# uController.net
KiCad netlist of a schematic drawn in Altium Designer
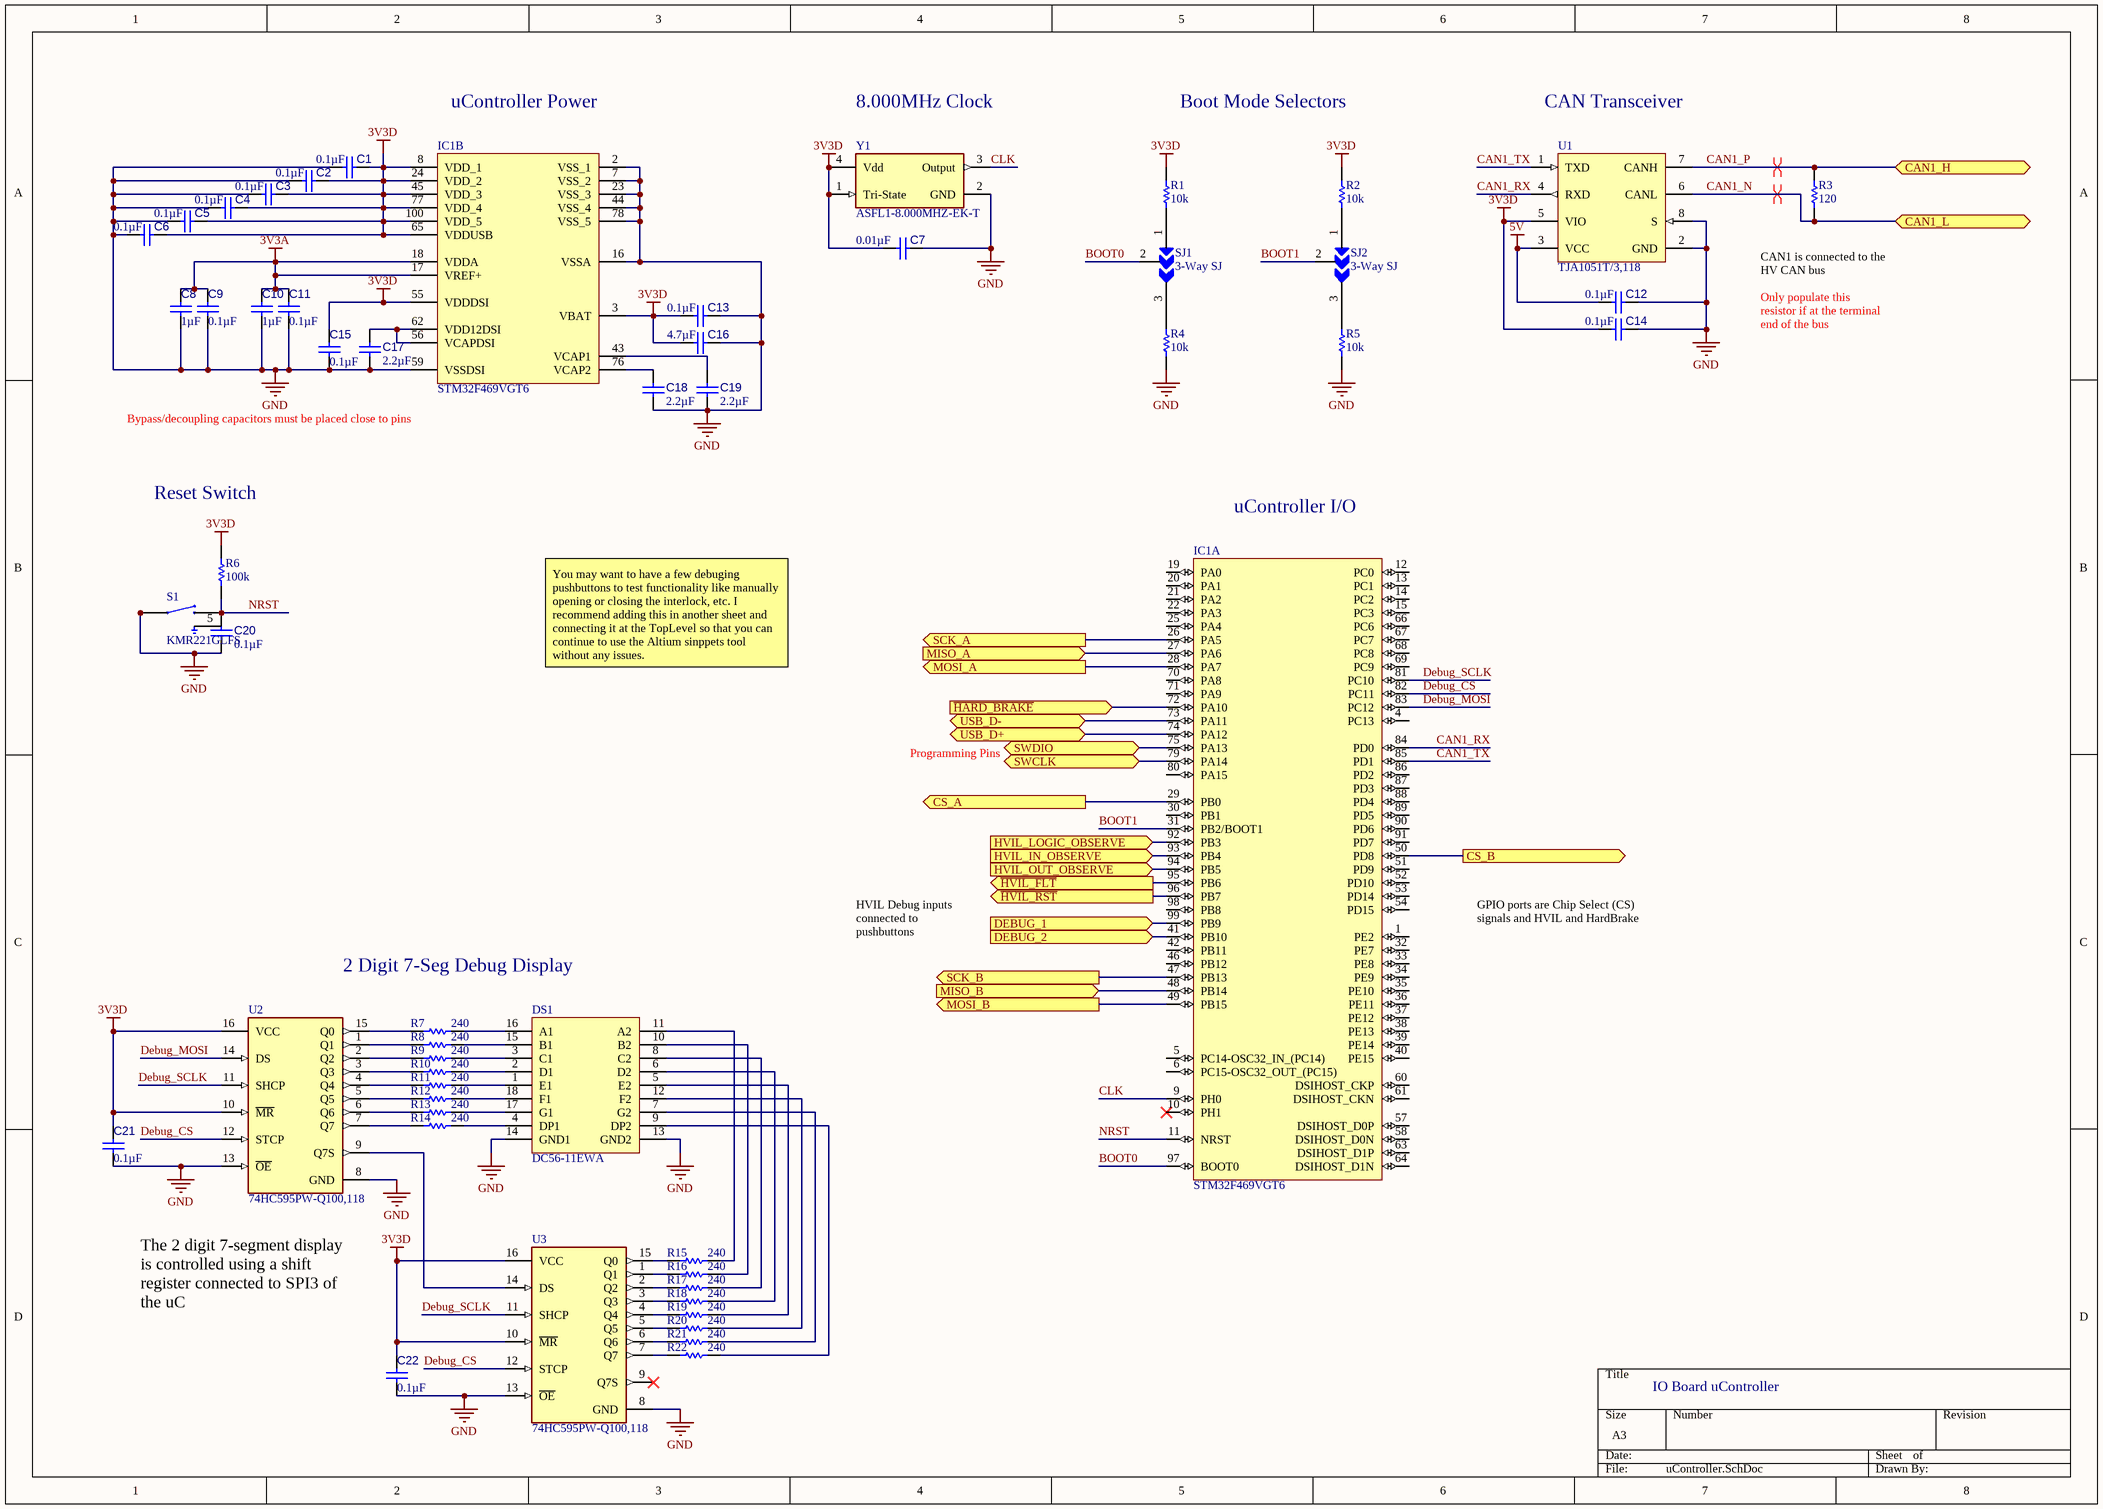
[diagram p0: uController.SchDoc]

(export (version "E")
  (design (tool "Eeschema 10.0.6"))
  (components
    (comp (ref "C1")
      (value "0.1µF")
      (footprint "CAPC2013X145X50ML20T25")
      (description "Chip Capacitor, 0.1 uF, +/-10%, 25 V, 0805 (2012 Metric)")
      (fields
        (field (name "MANUFACTURER") "KEMET")
        (field (name "MANUFACTURER PART NUMBER") "C0805C104K3RACTU")
      )
      (libsource (lib "Caltech FSAE") (part "CAP-NP-2"))
    )
    (comp (ref "C2")
      (value "0.1µF")
      (footprint "CAPC2013X145X50ML20T25")
      (description "Chip Capacitor, 0.1 uF, +/-10%, 25 V, 0805 (2012 Metric)")
      (fields
        (field (name "MANUFACTURER") "KEMET")
        (field (name "MANUFACTURER PART NUMBER") "C0805C104K3RACTU")
      )
      (libsource (lib "Caltech FSAE") (part "CAP-NP-2"))
    )
    (comp (ref "C3")
      (value "0.1µF")
      (footprint "CAPC2013X145X50ML20T25")
      (description "Chip Capacitor, 0.1 uF, +/-10%, 25 V, 0805 (2012 Metric)")
      (fields
        (field (name "MANUFACTURER") "KEMET")
        (field (name "MANUFACTURER PART NUMBER") "C0805C104K3RACTU")
      )
      (libsource (lib "Caltech FSAE") (part "CAP-NP-2"))
    )
    (comp (ref "C4")
      (value "0.1µF")
      (footprint "CAPC2013X145X50ML20T25")
      (description "Chip Capacitor, 0.1 uF, +/-10%, 25 V, 0805 (2012 Metric)")
      (fields
        (field (name "MANUFACTURER") "KEMET")
        (field (name "MANUFACTURER PART NUMBER") "C0805C104K3RACTU")
      )
      (libsource (lib "Caltech FSAE") (part "CAP-NP-2"))
    )
    (comp (ref "C5")
      (value "0.1µF")
      (footprint "CAPC2013X145X50ML20T25")
      (description "Chip Capacitor, 0.1 uF, +/-10%, 25 V, 0805 (2012 Metric)")
      (fields
        (field (name "MANUFACTURER") "KEMET")
        (field (name "MANUFACTURER PART NUMBER") "C0805C104K3RACTU")
      )
      (libsource (lib "Caltech FSAE") (part "CAP-NP-2"))
    )
    (comp (ref "C6")
      (value "0.1µF")
      (footprint "CAPC2013X145X50ML20T25")
      (description "Chip Capacitor, 0.1 uF, +/-10%, 25 V, 0805 (2012 Metric)")
      (fields
        (field (name "MANUFACTURER") "KEMET")
        (field (name "MANUFACTURER PART NUMBER") "C0805C104K3RACTU")
      )
      (libsource (lib "Caltech FSAE") (part "CAP-NP-2"))
    )
    (comp (ref "C7")
      (value "0.01µF")
      (footprint "CAPC2013X145X50ML20T25")
      (description "Chip Capacitor, 0.01 uF, +/-10%, 25 V, 0805 (2012 Metric)")
      (fields
        (field (name "MANUFACTURER") "KEMET")
        (field (name "MANUFACTURER PART NUMBER") "C0805C103K3RACTU")
      )
      (libsource (lib "Caltech FSAE") (part "CAP-NP-2"))
    )
    (comp (ref "C8")
      (value "1µF")
      (footprint "CAPC2013X145X50ML20T25")
      (description "Chip Capacitor, 1 uF, +/-10%, 25 V, 0805 (2012 Metric)")
      (fields
        (field (name "MANUFACTURER") "KEMET")
        (field (name "MANUFACTURER PART NUMBER") "C0805C105K3RACTU")
      )
      (libsource (lib "Caltech FSAE") (part "CAP-NP-2"))
    )
    (comp (ref "C9")
      (value "0.1µF")
      (footprint "CAPC2013X145X50ML20T25")
      (description "Chip Capacitor, 0.1 uF, +/-10%, 25 V, 0805 (2012 Metric)")
      (fields
        (field (name "MANUFACTURER") "KEMET")
        (field (name "MANUFACTURER PART NUMBER") "C0805C104K3RACTU")
      )
      (libsource (lib "Caltech FSAE") (part "CAP-NP-2"))
    )
    (comp (ref "C10")
      (value "1µF")
      (footprint "CAPC2013X145X50ML20T25")
      (description "Chip Capacitor, 1 uF, +/-10%, 25 V, 0805 (2012 Metric)")
      (fields
        (field (name "MANUFACTURER") "KEMET")
        (field (name "MANUFACTURER PART NUMBER") "C0805C105K3RACTU")
      )
      (libsource (lib "Caltech FSAE") (part "CAP-NP-2"))
    )
    (comp (ref "C11")
      (value "0.1µF")
      (footprint "CAPC2013X145X50ML20T25")
      (description "Chip Capacitor, 0.1 uF, +/-10%, 25 V, 0805 (2012 Metric)")
      (fields
        (field (name "MANUFACTURER") "KEMET")
        (field (name "MANUFACTURER PART NUMBER") "C0805C104K3RACTU")
      )
      (libsource (lib "Caltech FSAE") (part "CAP-NP-2"))
    )
    (comp (ref "C12")
      (value "0.1µF")
      (footprint "CAPC2013X145X50ML20T25")
      (description "Chip Capacitor, 0.1 uF, +/-10%, 25 V, 0805 (2012 Metric)")
      (fields
        (field (name "MANUFACTURER") "KEMET")
        (field (name "MANUFACTURER PART NUMBER") "C0805C104K3RACTU")
      )
      (libsource (lib "Caltech FSAE") (part "CAP-NP-2"))
    )
    (comp (ref "C13")
      (value "0.1µF")
      (footprint "CAPC2013X145X50ML20T25")
      (description "Chip Capacitor, 0.1 uF, +/-10%, 25 V, 0805 (2012 Metric)")
      (fields
        (field (name "MANUFACTURER") "KEMET")
        (field (name "MANUFACTURER PART NUMBER") "C0805C104K3RACTU")
      )
      (libsource (lib "Caltech FSAE") (part "CAP-NP-2"))
    )
    (comp (ref "C14")
      (value "0.1µF")
      (footprint "CAPC2013X145X50ML20T25")
      (description "Chip Capacitor, 0.1 uF, +/-10%, 25 V, 0805 (2012 Metric)")
      (fields
        (field (name "MANUFACTURER") "KEMET")
        (field (name "MANUFACTURER PART NUMBER") "C0805C104K3RACTU")
      )
      (libsource (lib "Caltech FSAE") (part "CAP-NP-2"))
    )
    (comp (ref "C15")
      (value "0.1µF")
      (footprint "CAPC2013X145X50ML20T25")
      (description "Chip Capacitor, 0.1 uF, +/-10%, 25 V, 0805 (2012 Metric)")
      (fields
        (field (name "MANUFACTURER") "KEMET")
        (field (name "MANUFACTURER PART NUMBER") "C0805C104K3RACTU")
      )
      (libsource (lib "Caltech FSAE") (part "CAP-NP-2"))
    )
    (comp (ref "C16")
      (value "4.7µF")
      (footprint "CAPC2013X145X50ML20T25")
      (description "Chip Capacitor, 4.7 uF, +/-10%, 25 V, 0805 (2012 Metric)")
      (fields
        (field (name "MANUFACTURER") "KEMET")
        (field (name "MANUFACTURER PART NUMBER") "C0805C475K3PACTU")
      )
      (libsource (lib "Caltech FSAE") (part "CAP-NP-2"))
    )
    (comp (ref "C17")
      (value "2.2µF")
      (footprint "CAPC2013X145X50ML20T25")
      (description "Chip Capacitor, 2.2 uF, +/-10%, 25 V, 0805 (2012 Metric)")
      (fields
        (field (name "MANUFACTURER") "KEMET")
        (field (name "MANUFACTURER PART NUMBER") "C0805C225K3RACTU")
      )
      (libsource (lib "Caltech FSAE") (part "CAP-NP-2"))
    )
    (comp (ref "C18")
      (value "2.2µF")
      (footprint "CAPC2013X145X50ML20T25")
      (description "Chip Capacitor, 2.2 uF, +/-10%, 25 V, 0805 (2012 Metric)")
      (fields
        (field (name "MANUFACTURER") "KEMET")
        (field (name "MANUFACTURER PART NUMBER") "C0805C225K3RACTU")
      )
      (libsource (lib "Caltech FSAE") (part "CAP-NP-2"))
    )
    (comp (ref "C19")
      (value "2.2µF")
      (footprint "CAPC2013X145X50ML20T25")
      (description "Chip Capacitor, 2.2 uF, +/-10%, 25 V, 0805 (2012 Metric)")
      (fields
        (field (name "MANUFACTURER") "KEMET")
        (field (name "MANUFACTURER PART NUMBER") "C0805C225K3RACTU")
      )
      (libsource (lib "Caltech FSAE") (part "CAP-NP-2"))
    )
    (comp (ref "C20")
      (value "0.1µF")
      (footprint "CAPC2013X145X50ML20T25")
      (description "Chip Capacitor, 0.1 uF, +/-10%, 25 V, 0805 (2012 Metric)")
      (fields
        (field (name "MANUFACTURER") "KEMET")
        (field (name "MANUFACTURER PART NUMBER") "C0805C104K3RACTU")
      )
      (libsource (lib "Caltech FSAE") (part "CAP-NP-2"))
    )
    (comp (ref "C21")
      (value "0.1µF")
      (footprint "CAPC2013X145X50ML20T25")
      (description "Chip Capacitor, 0.1 uF, +/-10%, 25 V, 0805 (2012 Metric)")
      (fields
        (field (name "MANUFACTURER") "KEMET")
        (field (name "MANUFACTURER PART NUMBER") "C0805C104K3RACTU")
      )
      (libsource (lib "Caltech FSAE") (part "CAP-NP-2"))
    )
    (comp (ref "C22")
      (value "0.1µF")
      (footprint "CAPC2013X145X50ML20T25")
      (description "Chip Capacitor, 0.1 uF, +/-10%, 25 V, 0805 (2012 Metric)")
      (fields
        (field (name "MANUFACTURER") "KEMET")
        (field (name "MANUFACTURER PART NUMBER") "C0805C104K3RACTU")
      )
      (libsource (lib "Caltech FSAE") (part "CAP-NP-2"))
    )
    (comp (ref "DS1")
      (value "DC56-11EWA")
      (footprint "uControllerTemplate2021:DIPS1524W75P254L2500H825Q18N")
      (description "Display")
      (fields (field (name "MOUSER PART NUMBER") "604-DC56-11EWA"))
      (libsource (lib "uControllerTemplate2021") (part "DC56-11EWA"))
    )
    (comp (ref "IC1")
      (value "STM32F469VGT6")
      (footprint "uControllerTemplate2021:QFP50P1600X1600X160-100N")
      (description "Integrated Circuit")
      (fields (field (name "MOUSER PART NUMBER") "511-STM32F469VGT6"))
      (libsource (lib "uControllerTemplate2021") (part "STM32F469VGT6"))
    )
    (comp (ref "R1")
      (value "10k")
      (footprint "RESC2013X50X35ML15T15")
      (description "Chip Resistor, 10k Ohm, +/- 1%, 125 mW, -55 to 155 degC, 0805 (2012 Metric)")
      (fields
        (field (name "MANUFACTURER") "Yageo")
        (field (name "MANUFACTURER PART NUMBER") "RC0805FR-0710KL")
      )
      (libsource (lib "Caltech FSAE") (part "RES-2"))
    )
    (comp (ref "R2")
      (value "10k")
      (footprint "RESC2013X50X35ML15T15")
      (description "Chip Resistor, 10k Ohm, +/- 1%, 125 mW, -55 to 155 degC, 0805 (2012 Metric)")
      (fields
        (field (name "MANUFACTURER") "Yageo")
        (field (name "MANUFACTURER PART NUMBER") "RC0805FR-0710KL")
      )
      (libsource (lib "Caltech FSAE") (part "RES-2"))
    )
    (comp (ref "R3")
      (value "120")
      (footprint "RESC2013X50X35ML15T15")
      (description "Chip Resistor, 120 Ohm, +/- 1%, 125 mW, -55 to 155 degC, 0805 (2012 Metric)")
      (fields
        (field (name "MANUFACTURER") "TE Connectivity")
        (field (name "MANUFACTURER PART NUMBER") "CRGCQ0805F120R")
      )
      (libsource (lib "Caltech FSAE") (part "RES-2"))
    )
    (comp (ref "R4")
      (value "10k")
      (footprint "RESC2013X50X35ML15T15")
      (description "Chip Resistor, 10k Ohm, +/- 1%, 125 mW, -55 to 155 degC, 0805 (2012 Metric)")
      (fields
        (field (name "MANUFACTURER") "Yageo")
        (field (name "MANUFACTURER PART NUMBER") "RC0805FR-0710KL")
      )
      (libsource (lib "Caltech FSAE") (part "RES-2"))
    )
    (comp (ref "R5")
      (value "10k")
      (footprint "RESC2013X50X35ML15T15")
      (description "Chip Resistor, 10k Ohm, +/- 1%, 125 mW, -55 to 155 degC, 0805 (2012 Metric)")
      (fields
        (field (name "MANUFACTURER") "Yageo")
        (field (name "MANUFACTURER PART NUMBER") "RC0805FR-0710KL")
      )
      (libsource (lib "Caltech FSAE") (part "RES-2"))
    )
    (comp (ref "R6")
      (value "100k")
      (footprint "RESC2013X50X35ML15T15")
      (description "Chip Resistor, 100k Ohm, +/- 1%, 125 mW, -55 to 155 degC, 0805 (2012 Metric)")
      (fields
        (field (name "MANUFACTURER") "Yageo")
        (field (name "MANUFACTURER PART NUMBER") "RC0805FR-07100KL")
      )
      (libsource (lib "Caltech FSAE") (part "RES-2"))
    )
    (comp (ref "R7")
      (value "240")
      (footprint "RESC2013X50X35ML15T15")
      (description "Chip Resistor, 240 Ohm, +/- 1%, 125 mW, -55 to 155 degC, 0805 (2012 Metric)")
      (fields
        (field (name "MANUFACTURER") "Panasonic")
        (field (name "MANUFACTURER PART NUMBER") "ERA-6AEB241V")
      )
      (libsource (lib "Caltech FSAE") (part "RES-2"))
    )
    (comp (ref "R8")
      (value "240")
      (footprint "RESC2013X50X35ML15T15")
      (description "Chip Resistor, 240 Ohm, +/- 1%, 125 mW, -55 to 155 degC, 0805 (2012 Metric)")
      (fields
        (field (name "MANUFACTURER") "Panasonic")
        (field (name "MANUFACTURER PART NUMBER") "ERA-6AEB241V")
      )
      (libsource (lib "Caltech FSAE") (part "RES-2"))
    )
    (comp (ref "R9")
      (value "240")
      (footprint "RESC2013X50X35ML15T15")
      (description "Chip Resistor, 240 Ohm, +/- 1%, 125 mW, -55 to 155 degC, 0805 (2012 Metric)")
      (fields
        (field (name "MANUFACTURER") "Panasonic")
        (field (name "MANUFACTURER PART NUMBER") "ERA-6AEB241V")
      )
      (libsource (lib "Caltech FSAE") (part "RES-2"))
    )
    (comp (ref "R10")
      (value "240")
      (footprint "RESC2013X50X35ML15T15")
      (description "Chip Resistor, 240 Ohm, +/- 1%, 125 mW, -55 to 155 degC, 0805 (2012 Metric)")
      (fields
        (field (name "MANUFACTURER") "Panasonic")
        (field (name "MANUFACTURER PART NUMBER") "ERA-6AEB241V")
      )
      (libsource (lib "Caltech FSAE") (part "RES-2"))
    )
    (comp (ref "R11")
      (value "240")
      (footprint "RESC2013X50X35ML15T15")
      (description "Chip Resistor, 240 Ohm, +/- 1%, 125 mW, -55 to 155 degC, 0805 (2012 Metric)")
      (fields
        (field (name "MANUFACTURER") "Panasonic")
        (field (name "MANUFACTURER PART NUMBER") "ERA-6AEB241V")
      )
      (libsource (lib "Caltech FSAE") (part "RES-2"))
    )
    (comp (ref "R12")
      (value "240")
      (footprint "RESC2013X50X35ML15T15")
      (description "Chip Resistor, 240 Ohm, +/- 1%, 125 mW, -55 to 155 degC, 0805 (2012 Metric)")
      (fields
        (field (name "MANUFACTURER") "Panasonic")
        (field (name "MANUFACTURER PART NUMBER") "ERA-6AEB241V")
      )
      (libsource (lib "Caltech FSAE") (part "RES-2"))
    )
    (comp (ref "R13")
      (value "240")
      (footprint "RESC2013X50X35ML15T15")
      (description "Chip Resistor, 240 Ohm, +/- 1%, 125 mW, -55 to 155 degC, 0805 (2012 Metric)")
      (fields
        (field (name "MANUFACTURER") "Panasonic")
        (field (name "MANUFACTURER PART NUMBER") "ERA-6AEB241V")
      )
      (libsource (lib "Caltech FSAE") (part "RES-2"))
    )
    (comp (ref "R14")
      (value "240")
      (footprint "RESC2013X50X35ML15T15")
      (description "Chip Resistor, 240 Ohm, +/- 1%, 125 mW, -55 to 155 degC, 0805 (2012 Metric)")
      (fields
        (field (name "MANUFACTURER") "Panasonic")
        (field (name "MANUFACTURER PART NUMBER") "ERA-6AEB241V")
      )
      (libsource (lib "Caltech FSAE") (part "RES-2"))
    )
    (comp (ref "R15")
      (value "240")
      (footprint "RESC2013X50X35ML15T15")
      (description "Chip Resistor, 240 Ohm, +/- 1%, 125 mW, -55 to 155 degC, 0805 (2012 Metric)")
      (fields
        (field (name "MANUFACTURER") "Panasonic")
        (field (name "MANUFACTURER PART NUMBER") "ERA-6AEB241V")
      )
      (libsource (lib "Caltech FSAE") (part "RES-2"))
    )
    (comp (ref "R16")
      (value "240")
      (footprint "RESC2013X50X35ML15T15")
      (description "Chip Resistor, 240 Ohm, +/- 1%, 125 mW, -55 to 155 degC, 0805 (2012 Metric)")
      (fields
        (field (name "MANUFACTURER") "Panasonic")
        (field (name "MANUFACTURER PART NUMBER") "ERA-6AEB241V")
      )
      (libsource (lib "Caltech FSAE") (part "RES-2"))
    )
    (comp (ref "R17")
      (value "240")
      (footprint "RESC2013X50X35ML15T15")
      (description "Chip Resistor, 240 Ohm, +/- 1%, 125 mW, -55 to 155 degC, 0805 (2012 Metric)")
      (fields
        (field (name "MANUFACTURER") "Panasonic")
        (field (name "MANUFACTURER PART NUMBER") "ERA-6AEB241V")
      )
      (libsource (lib "Caltech FSAE") (part "RES-2"))
    )
    (comp (ref "R18")
      (value "240")
      (footprint "RESC2013X50X35ML15T15")
      (description "Chip Resistor, 240 Ohm, +/- 1%, 125 mW, -55 to 155 degC, 0805 (2012 Metric)")
      (fields
        (field (name "MANUFACTURER") "Panasonic")
        (field (name "MANUFACTURER PART NUMBER") "ERA-6AEB241V")
      )
      (libsource (lib "Caltech FSAE") (part "RES-2"))
    )
    (comp (ref "R19")
      (value "240")
      (footprint "RESC2013X50X35ML15T15")
      (description "Chip Resistor, 240 Ohm, +/- 1%, 125 mW, -55 to 155 degC, 0805 (2012 Metric)")
      (fields
        (field (name "MANUFACTURER") "Panasonic")
        (field (name "MANUFACTURER PART NUMBER") "ERA-6AEB241V")
      )
      (libsource (lib "Caltech FSAE") (part "RES-2"))
    )
    (comp (ref "R20")
      (value "240")
      (footprint "RESC2013X50X35ML15T15")
      (description "Chip Resistor, 240 Ohm, +/- 1%, 125 mW, -55 to 155 degC, 0805 (2012 Metric)")
      (fields
        (field (name "MANUFACTURER") "Panasonic")
        (field (name "MANUFACTURER PART NUMBER") "ERA-6AEB241V")
      )
      (libsource (lib "Caltech FSAE") (part "RES-2"))
    )
    (comp (ref "R21")
      (value "240")
      (footprint "RESC2013X50X35ML15T15")
      (description "Chip Resistor, 240 Ohm, +/- 1%, 125 mW, -55 to 155 degC, 0805 (2012 Metric)")
      (fields
        (field (name "MANUFACTURER") "Panasonic")
        (field (name "MANUFACTURER PART NUMBER") "ERA-6AEB241V")
      )
      (libsource (lib "Caltech FSAE") (part "RES-2"))
    )
    (comp (ref "R22")
      (value "240")
      (footprint "RESC2013X50X35ML15T15")
      (description "Chip Resistor, 240 Ohm, +/- 1%, 125 mW, -55 to 155 degC, 0805 (2012 Metric)")
      (fields
        (field (name "MANUFACTURER") "Panasonic")
        (field (name "MANUFACTURER PART NUMBER") "ERA-6AEB241V")
      )
      (libsource (lib "Caltech FSAE") (part "RES-2"))
    )
    (comp (ref "S1")
      (value "KMR221GLFS")
      (footprint "SW_KMR221GLFS")
      (description "Tactile Switch SPST-NO Top Actuated Surface Mount")
      (fields (field (name "MF") "C&K"))
      (libsource (lib "uControllerTemplate2021") (part "KMR221GLFS"))
    )
    (comp (ref "SJ1")
      (value "3-Way SJ")
      (footprint "3-Way SJ")
      (description "3-Way Solder Jumper")
      (libsource (lib "uControllerTemplate2021") (part "3-Way SJ"))
    )
    (comp (ref "SJ2")
      (value "3-Way SJ")
      (footprint "3-Way SJ")
      (description "3-Way Solder Jumper")
      (libsource (lib "uControllerTemplate2021") (part "3-Way SJ"))
    )
    (comp (ref "U1")
      (value "TJA1051T/3,118")
      (footprint "NXP-SOIC-8_L")
      (description "High-Speed CAN Transceiver, 3 to 5 V, 8-Pin SOIC (SOT96-1), RoHS, Tape and Reel")
      (fields (field (name "MANUFACTURER") "NXP"))
      (libsource (lib "Altium Content Vault") (part "NXP-TJA1051T_3-SOIC-8"))
    )
    (comp (ref "U2")
      (value "74HC595PW-Q100,118")
      (footprint "FP-SOT403-1-MFG")
      (description "IC SHIFT REGISTER 8BIT 16TSSOP")
      (fields
        (field (name "MANUFACTURER") "Nexperia")
        (field (name "OCTOPART") "https://octopart.com/74hc595pw-q100%2C118-nexperia-78737379")
      )
      (libsource (lib "Altium Content Vault") (part "35014dcb5ee7218ec7bb80311b7c79e"))
    )
    (comp (ref "U3")
      (value "74HC595PW-Q100,118")
      (footprint "FP-SOT403-1-MFG")
      (description "IC SHIFT REGISTER 8BIT 16TSSOP")
      (fields
        (field (name "MANUFACTURER") "Nexperia")
        (field (name "OCTOPART") "https://octopart.com/74hc595pw-q100%2C118-nexperia-78737379")
      )
      (libsource (lib "Altium Content Vault") (part "35014dcb5ee7218ec7bb80311b7c79e"))
    )
    (comp (ref "Y1")
      (value "ASFL1-8.000MHZ-EK-T")
      (footprint "FP-ASFL1-MFG")
      (description "XTAL OSC XO 8.000MHZ HCMOS TTL")
      (fields
        (field (name "OCTOPART") "https://octopart.com/asfl1-16.384mhz-ec-t-abracon-317624")
        (field (name "MANUFACTURER") "Abracon")
      )
      (libsource (lib "Altium Content Vault") (part "4040d53610bfd20b859c6f7b79dc732"))
    )
  )
  (nets
    (net (code "1") (name "/BOOT0") (class "Default")
      (node (ref "IC1") (pin "97") (pinfunction "BOOT0_97") (pintype "bidirectional"))
      (node (ref "SJ1") (pin "2") (pinfunction "2_2") (pintype "passive"))
    )
    (net (code "2") (name "/BOOT1") (class "Default")
      (node (ref "IC1") (pin "31") (pinfunction "PB2/BOOT1_31") (pintype "bidirectional"))
      (node (ref "SJ2") (pin "2") (pinfunction "2_2") (pintype "passive"))
    )
    (net (code "3") (name "/CAN1_N") (class "Default")
      (node (ref "R3") (pin "1") (pinfunction "1_1") (pintype "passive"))
      (node (ref "U1") (pin "6") (pinfunction "CANL_6") (pintype "passive"))
    )
    (net (code "4") (name "/CAN1_P") (class "Default")
      (node (ref "R3") (pin "2") (pinfunction "2_2") (pintype "passive"))
      (node (ref "U1") (pin "7") (pinfunction "CANH_7") (pintype "passive"))
    )
    (net (code "5") (name "/CAN1_RX") (class "Default")
      (node (ref "IC1") (pin "84") (pinfunction "PD0_84") (pintype "bidirectional"))
      (node (ref "U1") (pin "4") (pinfunction "RXD_4") (pintype "output"))
    )
    (net (code "6") (name "/CAN1_TX") (class "Default")
      (node (ref "IC1") (pin "85") (pinfunction "PD1_85") (pintype "bidirectional"))
      (node (ref "U1") (pin "1") (pinfunction "TXD_1") (pintype "input"))
    )
    (net (code "7") (name "/CLK") (class "Default")
      (node (ref "IC1") (pin "9") (pinfunction "PH0_9") (pintype "bidirectional"))
      (node (ref "Y1") (pin "3") (pinfunction "Output_3") (pintype "output"))
    )
    (net (code "8") (name "/CS_A") (class "Default")
      (node (ref "IC1") (pin "29") (pinfunction "PB0_29") (pintype "bidirectional"))
    )
    (net (code "9") (name "/CS_B") (class "Default")
      (node (ref "IC1") (pin "50") (pinfunction "PD8_50") (pintype "bidirectional"))
    )
    (net (code "10") (name "/DEBUG_1") (class "Default")
      (node (ref "IC1") (pin "99") (pinfunction "PB9_99") (pintype "bidirectional"))
    )
    (net (code "11") (name "/DEBUG_2") (class "Default")
      (node (ref "IC1") (pin "41") (pinfunction "PB10_41") (pintype "bidirectional"))
    )
    (net (code "12") (name "/Debug_CS") (class "Default")
      (node (ref "IC1") (pin "82") (pinfunction "PC11_82") (pintype "bidirectional"))
      (node (ref "U2") (pin "12") (pinfunction "STCP_12") (pintype "input"))
      (node (ref "U3") (pin "12") (pinfunction "STCP_12") (pintype "input"))
    )
    (net (code "13") (name "/Debug_MOSI") (class "Default")
      (node (ref "IC1") (pin "83") (pinfunction "PC12_83") (pintype "bidirectional"))
      (node (ref "U2") (pin "14") (pinfunction "DS_14") (pintype "input"))
    )
    (net (code "14") (name "/Debug_SCLK") (class "Default")
      (node (ref "IC1") (pin "81") (pinfunction "PC10_81") (pintype "bidirectional"))
      (node (ref "U2") (pin "11") (pinfunction "SHCP_11") (pintype "input"))
      (node (ref "U3") (pin "11") (pinfunction "SHCP_11") (pintype "input"))
    )
    (net (code "15") (name "/HVIL_IN_OBSERVE") (class "Default")
      (node (ref "IC1") (pin "93") (pinfunction "PB4_93") (pintype "bidirectional"))
    )
    (net (code "16") (name "/HVIL_LOGIC_OBSERVE") (class "Default")
      (node (ref "IC1") (pin "92") (pinfunction "PB3_92") (pintype "bidirectional"))
    )
    (net (code "17") (name "/HVIL_OUT_OBSERVE") (class "Default")
      (node (ref "IC1") (pin "94") (pinfunction "PB5_94") (pintype "bidirectional"))
    )
    (net (code "18") (name "/MISO_A") (class "Default")
      (node (ref "IC1") (pin "27") (pinfunction "PA6_27") (pintype "bidirectional"))
    )
    (net (code "19") (name "/MISO_B") (class "Default")
      (node (ref "IC1") (pin "48") (pinfunction "PB14_48") (pintype "bidirectional"))
    )
    (net (code "20") (name "/MOSI_A") (class "Default")
      (node (ref "IC1") (pin "28") (pinfunction "PA7_28") (pintype "bidirectional"))
    )
    (net (code "21") (name "/MOSI_B") (class "Default")
      (node (ref "IC1") (pin "49") (pinfunction "PB15_49") (pintype "bidirectional"))
    )
    (net (code "22") (name "/NRST") (class "Default")
      (node (ref "C20") (pin "2") (pinfunction "2_2") (pintype "passive"))
      (node (ref "IC1") (pin "11") (pinfunction "NRST_11") (pintype "bidirectional"))
      (node (ref "R6") (pin "1") (pinfunction "1_1") (pintype "passive"))
      (node (ref "S1") (pin "2") (pinfunction "3_2") (pintype "passive"))
      (node (ref "S1") (pin "3") (pinfunction "3_3") (pintype "passive"))
    )
    (net (code "23") (name "/SCK_A") (class "Default")
      (node (ref "IC1") (pin "26") (pinfunction "PA5_26") (pintype "bidirectional"))
    )
    (net (code "24") (name "/SCK_B") (class "Default")
      (node (ref "IC1") (pin "47") (pinfunction "PB13_47") (pintype "bidirectional"))
    )
    (net (code "25") (name "/SWCLK") (class "Default")
      (node (ref "IC1") (pin "79") (pinfunction "PA14_79") (pintype "bidirectional"))
    )
    (net (code "26") (name "/SWDIO") (class "Default")
      (node (ref "IC1") (pin "75") (pinfunction "PA13_75") (pintype "bidirectional"))
    )
    (net (code "27") (name "/USB_D+") (class "Default")
      (node (ref "IC1") (pin "74") (pinfunction "PA12_74") (pintype "bidirectional"))
    )
    (net (code "28") (name "/USB_D-") (class "Default")
      (node (ref "IC1") (pin "73") (pinfunction "PA11_73") (pintype "bidirectional"))
    )
    (net (code "29") (name "/~{HARD_BRAKE}") (class "Default")
      (node (ref "IC1") (pin "72") (pinfunction "PA10_72") (pintype "bidirectional"))
    )
    (net (code "30") (name "/~{HVIL_FLT}") (class "Default")
      (node (ref "IC1") (pin "95") (pinfunction "PB6_95") (pintype "bidirectional"))
    )
    (net (code "31") (name "/~{HVIL_RST}") (class "Default")
      (node (ref "IC1") (pin "96") (pinfunction "PB7_96") (pintype "bidirectional"))
    )
    (net (code "32") (name "3V3A") (class "Default")
      (node (ref "C10") (pin "2") (pinfunction "2_2") (pintype "passive"))
      (node (ref "C11") (pin "1") (pinfunction "1_1") (pintype "passive"))
      (node (ref "C8") (pin "2") (pinfunction "2_2") (pintype "passive"))
      (node (ref "C9") (pin "1") (pinfunction "1_1") (pintype "passive"))
      (node (ref "IC1") (pin "17") (pinfunction "VREF+_17") (pintype "passive"))
      (node (ref "IC1") (pin "18") (pinfunction "VDDA_18") (pintype "passive"))
    )
    (net (code "33") (name "3V3D") (class "Default")
      (node (ref "C1") (pin "2") (pinfunction "2_2") (pintype "passive"))
      (node (ref "C13") (pin "1") (pinfunction "1_1") (pintype "passive"))
      (node (ref "C14") (pin "1") (pinfunction "1_1") (pintype "passive"))
      (node (ref "C15") (pin "1") (pinfunction "1_1") (pintype "passive"))
      (node (ref "C16") (pin "1") (pinfunction "1_1") (pintype "passive"))
      (node (ref "C2") (pin "2") (pinfunction "2_2") (pintype "passive"))
      (node (ref "C21") (pin "1") (pinfunction "1_1") (pintype "passive"))
      (node (ref "C22") (pin "1") (pinfunction "1_1") (pintype "passive"))
      (node (ref "C3") (pin "2") (pinfunction "2_2") (pintype "passive"))
      (node (ref "C4") (pin "2") (pinfunction "2_2") (pintype "passive"))
      (node (ref "C5") (pin "2") (pinfunction "2_2") (pintype "passive"))
      (node (ref "C6") (pin "2") (pinfunction "2_2") (pintype "passive"))
      (node (ref "C7") (pin "1") (pinfunction "1_1") (pintype "passive"))
      (node (ref "IC1") (pin "100") (pinfunction "VDD_5_100") (pintype "passive"))
      (node (ref "IC1") (pin "24") (pinfunction "VDD_2_24") (pintype "passive"))
      (node (ref "IC1") (pin "3") (pinfunction "VBAT_3") (pintype "passive"))
      (node (ref "IC1") (pin "45") (pinfunction "VDD_3_45") (pintype "passive"))
      (node (ref "IC1") (pin "55") (pinfunction "VDDDSI_55") (pintype "passive"))
      (node (ref "IC1") (pin "65") (pinfunction "VDDUSB_65") (pintype "passive"))
      (node (ref "IC1") (pin "77") (pinfunction "VDD_4_77") (pintype "passive"))
      (node (ref "IC1") (pin "8") (pinfunction "VDD_1_8") (pintype "passive"))
      (node (ref "R1") (pin "2") (pinfunction "2_2") (pintype "passive"))
      (node (ref "R2") (pin "2") (pinfunction "2_2") (pintype "passive"))
      (node (ref "R6") (pin "2") (pinfunction "2_2") (pintype "passive"))
      (node (ref "U1") (pin "5") (pinfunction "VIO_5") (pintype "power_in"))
      (node (ref "U2") (pin "10") (pinfunction "~{MR}_10") (pintype "input"))
      (node (ref "U2") (pin "16") (pinfunction "VCC_16") (pintype "power_in"))
      (node (ref "U3") (pin "10") (pinfunction "~{MR}_10") (pintype "input"))
      (node (ref "U3") (pin "16") (pinfunction "VCC_16") (pintype "power_in"))
      (node (ref "Y1") (pin "1") (pinfunction "Tri-State_1") (pintype "input"))
      (node (ref "Y1") (pin "4") (pinfunction "Vdd_4") (pintype "power_in"))
    )
    (net (code "34") (name "5V") (class "Default")
      (node (ref "C12") (pin "1") (pinfunction "1_1") (pintype "passive"))
      (node (ref "U1") (pin "3") (pinfunction "VCC_3") (pintype "power_in"))
    )
    (net (code "35") (name "GND") (class "Default")
      (node (ref "C1") (pin "1") (pinfunction "1_1") (pintype "passive"))
      (node (ref "C10") (pin "1") (pinfunction "1_1") (pintype "passive"))
      (node (ref "C11") (pin "2") (pinfunction "2_2") (pintype "passive"))
      (node (ref "C12") (pin "2") (pinfunction "2_2") (pintype "passive"))
      (node (ref "C13") (pin "2") (pinfunction "2_2") (pintype "passive"))
      (node (ref "C14") (pin "2") (pinfunction "2_2") (pintype "passive"))
      (node (ref "C15") (pin "2") (pinfunction "2_2") (pintype "passive"))
      (node (ref "C16") (pin "2") (pinfunction "2_2") (pintype "passive"))
      (node (ref "C17") (pin "1") (pinfunction "1_1") (pintype "passive"))
      (node (ref "C18") (pin "1") (pinfunction "1_1") (pintype "passive"))
      (node (ref "C19") (pin "1") (pinfunction "1_1") (pintype "passive"))
      (node (ref "C2") (pin "1") (pinfunction "1_1") (pintype "passive"))
      (node (ref "C20") (pin "1") (pinfunction "1_1") (pintype "passive"))
      (node (ref "C21") (pin "2") (pinfunction "2_2") (pintype "passive"))
      (node (ref "C22") (pin "2") (pinfunction "2_2") (pintype "passive"))
      (node (ref "C3") (pin "1") (pinfunction "1_1") (pintype "passive"))
      (node (ref "C4") (pin "1") (pinfunction "1_1") (pintype "passive"))
      (node (ref "C5") (pin "1") (pinfunction "1_1") (pintype "passive"))
      (node (ref "C6") (pin "1") (pinfunction "1_1") (pintype "passive"))
      (node (ref "C7") (pin "2") (pinfunction "2_2") (pintype "passive"))
      (node (ref "C8") (pin "1") (pinfunction "1_1") (pintype "passive"))
      (node (ref "C9") (pin "2") (pinfunction "2_2") (pintype "passive"))
      (node (ref "DS1") (pin "13") (pinfunction "GND2_13") (pintype "passive"))
      (node (ref "DS1") (pin "14") (pinfunction "GND1_14") (pintype "passive"))
      (node (ref "IC1") (pin "16") (pinfunction "VSSA_16") (pintype "passive"))
      (node (ref "IC1") (pin "2") (pinfunction "VSS_1_2") (pintype "passive"))
      (node (ref "IC1") (pin "23") (pinfunction "VSS_3_23") (pintype "passive"))
      (node (ref "IC1") (pin "44") (pinfunction "VSS_4_44") (pintype "passive"))
      (node (ref "IC1") (pin "59") (pinfunction "VSSDSI_59") (pintype "passive"))
      (node (ref "IC1") (pin "7") (pinfunction "VSS_2_7") (pintype "passive"))
      (node (ref "IC1") (pin "78") (pinfunction "VSS_5_78") (pintype "passive"))
      (node (ref "R4") (pin "1") (pinfunction "1_1") (pintype "passive"))
      (node (ref "R5") (pin "1") (pinfunction "1_1") (pintype "passive"))
      (node (ref "S1") (pin "1") (pinfunction "1_1") (pintype "passive"))
      (node (ref "S1") (pin "4") (pinfunction "1_4") (pintype "passive"))
      (node (ref "U1") (pin "2") (pinfunction "GND_2") (pintype "power_in"))
      (node (ref "U1") (pin "8") (pinfunction "S_8") (pintype "input"))
      (node (ref "U2") (pin "13") (pinfunction "~{OE}_13") (pintype "input"))
      (node (ref "U2") (pin "8") (pinfunction "GND_8") (pintype "power_in"))
      (node (ref "U3") (pin "13") (pinfunction "~{OE}_13") (pintype "input"))
      (node (ref "U3") (pin "8") (pinfunction "GND_8") (pintype "power_in"))
      (node (ref "Y1") (pin "2") (pinfunction "GND_2") (pintype "power_in"))
    )
    (net (code "36") (name "Net-(DS1-A1)") (class "Default")
      (node (ref "DS1") (pin "16") (pinfunction "A1_16") (pintype "passive"))
      (node (ref "R7") (pin "1") (pinfunction "1_1") (pintype "passive"))
    )
    (net (code "37") (name "Net-(DS1-A2)") (class "Default")
      (node (ref "DS1") (pin "11") (pinfunction "A2_11") (pintype "passive"))
      (node (ref "R15") (pin "1") (pinfunction "1_1") (pintype "passive"))
    )
    (net (code "38") (name "Net-(DS1-B1)") (class "Default")
      (node (ref "DS1") (pin "15") (pinfunction "B1_15") (pintype "passive"))
      (node (ref "R8") (pin "1") (pinfunction "1_1") (pintype "passive"))
    )
    (net (code "39") (name "Net-(DS1-B2)") (class "Default")
      (node (ref "DS1") (pin "10") (pinfunction "B2_10") (pintype "passive"))
      (node (ref "R16") (pin "1") (pinfunction "1_1") (pintype "passive"))
    )
    (net (code "40") (name "Net-(DS1-C1)") (class "Default")
      (node (ref "DS1") (pin "3") (pinfunction "C1_3") (pintype "passive"))
      (node (ref "R9") (pin "1") (pinfunction "1_1") (pintype "passive"))
    )
    (net (code "41") (name "Net-(DS1-C2)") (class "Default")
      (node (ref "DS1") (pin "8") (pinfunction "C2_8") (pintype "passive"))
      (node (ref "R17") (pin "1") (pinfunction "1_1") (pintype "passive"))
    )
    (net (code "42") (name "Net-(DS1-D1)") (class "Default")
      (node (ref "DS1") (pin "2") (pinfunction "D1_2") (pintype "passive"))
      (node (ref "R10") (pin "1") (pinfunction "1_1") (pintype "passive"))
    )
    (net (code "43") (name "Net-(DS1-D2)") (class "Default")
      (node (ref "DS1") (pin "6") (pinfunction "D2_6") (pintype "passive"))
      (node (ref "R18") (pin "1") (pinfunction "1_1") (pintype "passive"))
    )
    (net (code "44") (name "Net-(DS1-DP1)") (class "Default")
      (node (ref "DS1") (pin "4") (pinfunction "DP1_4") (pintype "passive"))
      (node (ref "R14") (pin "1") (pinfunction "1_1") (pintype "passive"))
    )
    (net (code "45") (name "Net-(DS1-DP2)") (class "Default")
      (node (ref "DS1") (pin "9") (pinfunction "DP2_9") (pintype "passive"))
      (node (ref "R22") (pin "1") (pinfunction "1_1") (pintype "passive"))
    )
    (net (code "46") (name "Net-(DS1-E1)") (class "Default")
      (node (ref "DS1") (pin "1") (pinfunction "E1_1") (pintype "passive"))
      (node (ref "R11") (pin "1") (pinfunction "1_1") (pintype "passive"))
    )
    (net (code "47") (name "Net-(DS1-E2)") (class "Default")
      (node (ref "DS1") (pin "5") (pinfunction "E2_5") (pintype "passive"))
      (node (ref "R19") (pin "1") (pinfunction "1_1") (pintype "passive"))
    )
    (net (code "48") (name "Net-(DS1-F1)") (class "Default")
      (node (ref "DS1") (pin "18") (pinfunction "F1_18") (pintype "passive"))
      (node (ref "R12") (pin "1") (pinfunction "1_1") (pintype "passive"))
    )
    (net (code "49") (name "Net-(DS1-F2)") (class "Default")
      (node (ref "DS1") (pin "12") (pinfunction "F2_12") (pintype "passive"))
      (node (ref "R20") (pin "1") (pinfunction "1_1") (pintype "passive"))
    )
    (net (code "50") (name "Net-(DS1-G1)") (class "Default")
      (node (ref "DS1") (pin "17") (pinfunction "G1_17") (pintype "passive"))
      (node (ref "R13") (pin "1") (pinfunction "1_1") (pintype "passive"))
    )
    (net (code "51") (name "Net-(DS1-G2)") (class "Default")
      (node (ref "DS1") (pin "7") (pinfunction "G2_7") (pintype "passive"))
      (node (ref "R21") (pin "1") (pinfunction "1_1") (pintype "passive"))
    )
    (net (code "52") (name "Net-(IC1B-VCAP1)") (class "Default")
      (node (ref "C19") (pin "2") (pinfunction "2_2") (pintype "passive"))
      (node (ref "IC1") (pin "43") (pinfunction "VCAP1_43") (pintype "passive"))
    )
    (net (code "53") (name "Net-(IC1B-VCAP2)") (class "Default")
      (node (ref "C18") (pin "2") (pinfunction "2_2") (pintype "passive"))
      (node (ref "IC1") (pin "76") (pinfunction "VCAP2_76") (pintype "passive"))
    )
    (net (code "54") (name "Net-(IC1B-VCAPDSI)") (class "Default")
      (node (ref "C17") (pin "2") (pinfunction "2_2") (pintype "passive"))
      (node (ref "IC1") (pin "56") (pinfunction "VCAPDSI_56") (pintype "passive"))
      (node (ref "IC1") (pin "62") (pinfunction "VDD12DSI_62") (pintype "passive"))
    )
    (net (code "55") (name "Net-(R1-Pad1)") (class "Default")
      (node (ref "R1") (pin "1") (pinfunction "1_1") (pintype "passive"))
      (node (ref "SJ1") (pin "1") (pinfunction "1_1") (pintype "passive"))
    )
    (net (code "56") (name "Net-(R2-Pad1)") (class "Default")
      (node (ref "R2") (pin "1") (pinfunction "1_1") (pintype "passive"))
      (node (ref "SJ2") (pin "1") (pinfunction "1_1") (pintype "passive"))
    )
    (net (code "57") (name "Net-(R4-Pad2)") (class "Default")
      (node (ref "R4") (pin "2") (pinfunction "2_2") (pintype "passive"))
      (node (ref "SJ1") (pin "3") (pinfunction "3_3") (pintype "passive"))
    )
    (net (code "58") (name "Net-(R5-Pad2)") (class "Default")
      (node (ref "R5") (pin "2") (pinfunction "2_2") (pintype "passive"))
      (node (ref "SJ2") (pin "3") (pinfunction "3_3") (pintype "passive"))
    )
    (net (code "59") (name "Net-(U2-Q0)") (class "Default")
      (node (ref "R7") (pin "2") (pinfunction "2_2") (pintype "passive"))
      (node (ref "U2") (pin "15") (pinfunction "Q0_15") (pintype "output"))
    )
    (net (code "60") (name "Net-(U2-Q1)") (class "Default")
      (node (ref "R8") (pin "2") (pinfunction "2_2") (pintype "passive"))
      (node (ref "U2") (pin "1") (pinfunction "Q1_1") (pintype "output"))
    )
    (net (code "61") (name "Net-(U2-Q2)") (class "Default")
      (node (ref "R9") (pin "2") (pinfunction "2_2") (pintype "passive"))
      (node (ref "U2") (pin "2") (pinfunction "Q2_2") (pintype "output"))
    )
    (net (code "62") (name "Net-(U2-Q3)") (class "Default")
      (node (ref "R10") (pin "2") (pinfunction "2_2") (pintype "passive"))
      (node (ref "U2") (pin "3") (pinfunction "Q3_3") (pintype "output"))
    )
    (net (code "63") (name "Net-(U2-Q4)") (class "Default")
      (node (ref "R11") (pin "2") (pinfunction "2_2") (pintype "passive"))
      (node (ref "U2") (pin "4") (pinfunction "Q4_4") (pintype "output"))
    )
    (net (code "64") (name "Net-(U2-Q5)") (class "Default")
      (node (ref "R12") (pin "2") (pinfunction "2_2") (pintype "passive"))
      (node (ref "U2") (pin "5") (pinfunction "Q5_5") (pintype "output"))
    )
    (net (code "65") (name "Net-(U2-Q6)") (class "Default")
      (node (ref "R13") (pin "2") (pinfunction "2_2") (pintype "passive"))
      (node (ref "U2") (pin "6") (pinfunction "Q6_6") (pintype "output"))
    )
    (net (code "66") (name "Net-(U2-Q7)") (class "Default")
      (node (ref "R14") (pin "2") (pinfunction "2_2") (pintype "passive"))
      (node (ref "U2") (pin "7") (pinfunction "Q7_7") (pintype "output"))
    )
    (net (code "67") (name "Net-(U2-Q7S)") (class "Default")
      (node (ref "U2") (pin "9") (pinfunction "Q7S_9") (pintype "output"))
      (node (ref "U3") (pin "14") (pinfunction "DS_14") (pintype "input"))
    )
    (net (code "68") (name "Net-(U3-Q0)") (class "Default")
      (node (ref "R15") (pin "2") (pinfunction "2_2") (pintype "passive"))
      (node (ref "U3") (pin "15") (pinfunction "Q0_15") (pintype "output"))
    )
    (net (code "69") (name "Net-(U3-Q1)") (class "Default")
      (node (ref "R16") (pin "2") (pinfunction "2_2") (pintype "passive"))
      (node (ref "U3") (pin "1") (pinfunction "Q1_1") (pintype "output"))
    )
    (net (code "70") (name "Net-(U3-Q2)") (class "Default")
      (node (ref "R17") (pin "2") (pinfunction "2_2") (pintype "passive"))
      (node (ref "U3") (pin "2") (pinfunction "Q2_2") (pintype "output"))
    )
    (net (code "71") (name "Net-(U3-Q3)") (class "Default")
      (node (ref "R18") (pin "2") (pinfunction "2_2") (pintype "passive"))
      (node (ref "U3") (pin "3") (pinfunction "Q3_3") (pintype "output"))
    )
    (net (code "72") (name "Net-(U3-Q4)") (class "Default")
      (node (ref "R19") (pin "2") (pinfunction "2_2") (pintype "passive"))
      (node (ref "U3") (pin "4") (pinfunction "Q4_4") (pintype "output"))
    )
    (net (code "73") (name "Net-(U3-Q5)") (class "Default")
      (node (ref "R20") (pin "2") (pinfunction "2_2") (pintype "passive"))
      (node (ref "U3") (pin "5") (pinfunction "Q5_5") (pintype "output"))
    )
    (net (code "74") (name "Net-(U3-Q6)") (class "Default")
      (node (ref "R21") (pin "2") (pinfunction "2_2") (pintype "passive"))
      (node (ref "U3") (pin "6") (pinfunction "Q6_6") (pintype "output"))
    )
    (net (code "75") (name "Net-(U3-Q7)") (class "Default")
      (node (ref "R22") (pin "2") (pinfunction "2_2") (pintype "passive"))
      (node (ref "U3") (pin "7") (pinfunction "Q7_7") (pintype "output"))
    )
    (net (code "76") (name "unconnected-(IC1A-DSIHOST_CKN-Pad61)") (class "Default")
      (node (ref "IC1") (pin "61") (pinfunction "DSIHOST_CKN_61") (pintype "bidirectional"))
    )
    (net (code "77") (name "unconnected-(IC1A-DSIHOST_CKP-Pad60)") (class "Default")
      (node (ref "IC1") (pin "60") (pinfunction "DSIHOST_CKP_60") (pintype "bidirectional"))
    )
    (net (code "78") (name "unconnected-(IC1A-DSIHOST_D0N-Pad58)") (class "Default")
      (node (ref "IC1") (pin "58") (pinfunction "DSIHOST_D0N_58") (pintype "bidirectional"))
    )
    (net (code "79") (name "unconnected-(IC1A-DSIHOST_D0P-Pad57)") (class "Default")
      (node (ref "IC1") (pin "57") (pinfunction "DSIHOST_D0P_57") (pintype "bidirectional"))
    )
    (net (code "80") (name "unconnected-(IC1A-DSIHOST_D1N-Pad64)") (class "Default")
      (node (ref "IC1") (pin "64") (pinfunction "DSIHOST_D1N_64") (pintype "bidirectional"))
    )
    (net (code "81") (name "unconnected-(IC1A-DSIHOST_D1P-Pad63)") (class "Default")
      (node (ref "IC1") (pin "63") (pinfunction "DSIHOST_D1P_63") (pintype "bidirectional"))
    )
    (net (code "82") (name "unconnected-(IC1A-PA0-Pad19)") (class "Default")
      (node (ref "IC1") (pin "19") (pinfunction "PA0_19") (pintype "bidirectional"))
    )
    (net (code "83") (name "unconnected-(IC1A-PA1-Pad20)") (class "Default")
      (node (ref "IC1") (pin "20") (pinfunction "PA1_20") (pintype "bidirectional"))
    )
    (net (code "84") (name "unconnected-(IC1A-PA2-Pad21)") (class "Default")
      (node (ref "IC1") (pin "21") (pinfunction "PA2_21") (pintype "bidirectional"))
    )
    (net (code "85") (name "unconnected-(IC1A-PA3-Pad22)") (class "Default")
      (node (ref "IC1") (pin "22") (pinfunction "PA3_22") (pintype "bidirectional"))
    )
    (net (code "86") (name "unconnected-(IC1A-PA4-Pad25)") (class "Default")
      (node (ref "IC1") (pin "25") (pinfunction "PA4_25") (pintype "bidirectional"))
    )
    (net (code "87") (name "unconnected-(IC1A-PA8-Pad70)") (class "Default")
      (node (ref "IC1") (pin "70") (pinfunction "PA8_70") (pintype "bidirectional"))
    )
    (net (code "88") (name "unconnected-(IC1A-PA9-Pad71)") (class "Default")
      (node (ref "IC1") (pin "71") (pinfunction "PA9_71") (pintype "bidirectional"))
    )
    (net (code "89") (name "unconnected-(IC1A-PA15-Pad80)") (class "Default")
      (node (ref "IC1") (pin "80") (pinfunction "PA15_80") (pintype "bidirectional"))
    )
    (net (code "90") (name "unconnected-(IC1A-PB1-Pad30)") (class "Default")
      (node (ref "IC1") (pin "30") (pinfunction "PB1_30") (pintype "bidirectional"))
    )
    (net (code "91") (name "unconnected-(IC1A-PB8-Pad98)") (class "Default")
      (node (ref "IC1") (pin "98") (pinfunction "PB8_98") (pintype "bidirectional"))
    )
    (net (code "92") (name "unconnected-(IC1A-PB11-Pad42)") (class "Default")
      (node (ref "IC1") (pin "42") (pinfunction "PB11_42") (pintype "bidirectional"))
    )
    (net (code "93") (name "unconnected-(IC1A-PB12-Pad46)") (class "Default")
      (node (ref "IC1") (pin "46") (pinfunction "PB12_46") (pintype "bidirectional"))
    )
    (net (code "94") (name "unconnected-(IC1A-PC0-Pad12)") (class "Default")
      (node (ref "IC1") (pin "12") (pinfunction "PC0_12") (pintype "bidirectional"))
    )
    (net (code "95") (name "unconnected-(IC1A-PC1-Pad13)") (class "Default")
      (node (ref "IC1") (pin "13") (pinfunction "PC1_13") (pintype "bidirectional"))
    )
    (net (code "96") (name "unconnected-(IC1A-PC2-Pad14)") (class "Default")
      (node (ref "IC1") (pin "14") (pinfunction "PC2_14") (pintype "bidirectional"))
    )
    (net (code "97") (name "unconnected-(IC1A-PC3-Pad15)") (class "Default")
      (node (ref "IC1") (pin "15") (pinfunction "PC3_15") (pintype "bidirectional"))
    )
    (net (code "98") (name "unconnected-(IC1A-PC6-Pad66)") (class "Default")
      (node (ref "IC1") (pin "66") (pinfunction "PC6_66") (pintype "bidirectional"))
    )
    (net (code "99") (name "unconnected-(IC1A-PC7-Pad67)") (class "Default")
      (node (ref "IC1") (pin "67") (pinfunction "PC7_67") (pintype "bidirectional"))
    )
    (net (code "100") (name "unconnected-(IC1A-PC8-Pad68)") (class "Default")
      (node (ref "IC1") (pin "68") (pinfunction "PC8_68") (pintype "bidirectional"))
    )
    (net (code "101") (name "unconnected-(IC1A-PC9-Pad69)") (class "Default")
      (node (ref "IC1") (pin "69") (pinfunction "PC9_69") (pintype "bidirectional"))
    )
    (net (code "102") (name "unconnected-(IC1A-PC13-Pad4)") (class "Default")
      (node (ref "IC1") (pin "4") (pinfunction "PC13_4") (pintype "bidirectional"))
    )
    (net (code "103") (name "unconnected-(IC1A-PC14-OSC32_IN_(PC14)-Pad5)") (class "Default")
      (node (ref "IC1") (pin "5") (pinfunction "PC14-OSC32_IN_(PC14)_5") (pintype "bidirectional"))
    )
    (net (code "104") (name "unconnected-(IC1A-PC15-OSC32_OUT_(PC15)-Pad6)") (class "Default")
      (node (ref "IC1") (pin "6") (pinfunction "PC15-OSC32_OUT_(PC15)_6") (pintype "bidirectional"))
    )
    (net (code "105") (name "unconnected-(IC1A-PD2-Pad86)") (class "Default")
      (node (ref "IC1") (pin "86") (pinfunction "PD2_86") (pintype "bidirectional"))
    )
    (net (code "106") (name "unconnected-(IC1A-PD3-Pad87)") (class "Default")
      (node (ref "IC1") (pin "87") (pinfunction "PD3_87") (pintype "bidirectional"))
    )
    (net (code "107") (name "unconnected-(IC1A-PD4-Pad88)") (class "Default")
      (node (ref "IC1") (pin "88") (pinfunction "PD4_88") (pintype "bidirectional"))
    )
    (net (code "108") (name "unconnected-(IC1A-PD5-Pad89)") (class "Default")
      (node (ref "IC1") (pin "89") (pinfunction "PD5_89") (pintype "bidirectional"))
    )
    (net (code "109") (name "unconnected-(IC1A-PD6-Pad90)") (class "Default")
      (node (ref "IC1") (pin "90") (pinfunction "PD6_90") (pintype "bidirectional"))
    )
    (net (code "110") (name "unconnected-(IC1A-PD7-Pad91)") (class "Default")
      (node (ref "IC1") (pin "91") (pinfunction "PD7_91") (pintype "bidirectional"))
    )
    (net (code "111") (name "unconnected-(IC1A-PD9-Pad51)") (class "Default")
      (node (ref "IC1") (pin "51") (pinfunction "PD9_51") (pintype "bidirectional"))
    )
    (net (code "112") (name "unconnected-(IC1A-PD10-Pad52)") (class "Default")
      (node (ref "IC1") (pin "52") (pinfunction "PD10_52") (pintype "bidirectional"))
    )
    (net (code "113") (name "unconnected-(IC1A-PD14-Pad53)") (class "Default")
      (node (ref "IC1") (pin "53") (pinfunction "PD14_53") (pintype "bidirectional"))
    )
    (net (code "114") (name "unconnected-(IC1A-PD15-Pad54)") (class "Default")
      (node (ref "IC1") (pin "54") (pinfunction "PD15_54") (pintype "bidirectional"))
    )
    (net (code "115") (name "unconnected-(IC1A-PE2-Pad1)") (class "Default")
      (node (ref "IC1") (pin "1") (pinfunction "PE2_1") (pintype "bidirectional"))
    )
    (net (code "116") (name "unconnected-(IC1A-PE7-Pad32)") (class "Default")
      (node (ref "IC1") (pin "32") (pinfunction "PE7_32") (pintype "bidirectional"))
    )
    (net (code "117") (name "unconnected-(IC1A-PE8-Pad33)") (class "Default")
      (node (ref "IC1") (pin "33") (pinfunction "PE8_33") (pintype "bidirectional"))
    )
    (net (code "118") (name "unconnected-(IC1A-PE9-Pad34)") (class "Default")
      (node (ref "IC1") (pin "34") (pinfunction "PE9_34") (pintype "bidirectional"))
    )
    (net (code "119") (name "unconnected-(IC1A-PE10-Pad35)") (class "Default")
      (node (ref "IC1") (pin "35") (pinfunction "PE10_35") (pintype "bidirectional"))
    )
    (net (code "120") (name "unconnected-(IC1A-PE11-Pad36)") (class "Default")
      (node (ref "IC1") (pin "36") (pinfunction "PE11_36") (pintype "bidirectional"))
    )
    (net (code "121") (name "unconnected-(IC1A-PE12-Pad37)") (class "Default")
      (node (ref "IC1") (pin "37") (pinfunction "PE12_37") (pintype "bidirectional"))
    )
    (net (code "122") (name "unconnected-(IC1A-PE13-Pad38)") (class "Default")
      (node (ref "IC1") (pin "38") (pinfunction "PE13_38") (pintype "bidirectional"))
    )
    (net (code "123") (name "unconnected-(IC1A-PE14-Pad39)") (class "Default")
      (node (ref "IC1") (pin "39") (pinfunction "PE14_39") (pintype "bidirectional"))
    )
    (net (code "124") (name "unconnected-(IC1A-PE15-Pad40)") (class "Default")
      (node (ref "IC1") (pin "40") (pinfunction "PE15_40") (pintype "bidirectional"))
    )
    (net (code "125") (name "unconnected-(IC1A-PH1-Pad10)") (class "Default")
      (node (ref "IC1") (pin "10") (pinfunction "PH1_10") (pintype "bidirectional+no_connect"))
    )
    (net (code "126") (name "unconnected-(S1-Pad5)") (class "Default")
      (node (ref "S1") (pin "5") (pinfunction "5_5") (pintype "passive"))
    )
    (net (code "127") (name "unconnected-(U3-Q7S-Pad9)") (class "Default")
      (node (ref "U3") (pin "9") (pinfunction "Q7S_9") (pintype "output+no_connect"))
    )
  )
)
